# Sheet2.net
KiCad netlist of a schematic drawn in Altium Designer
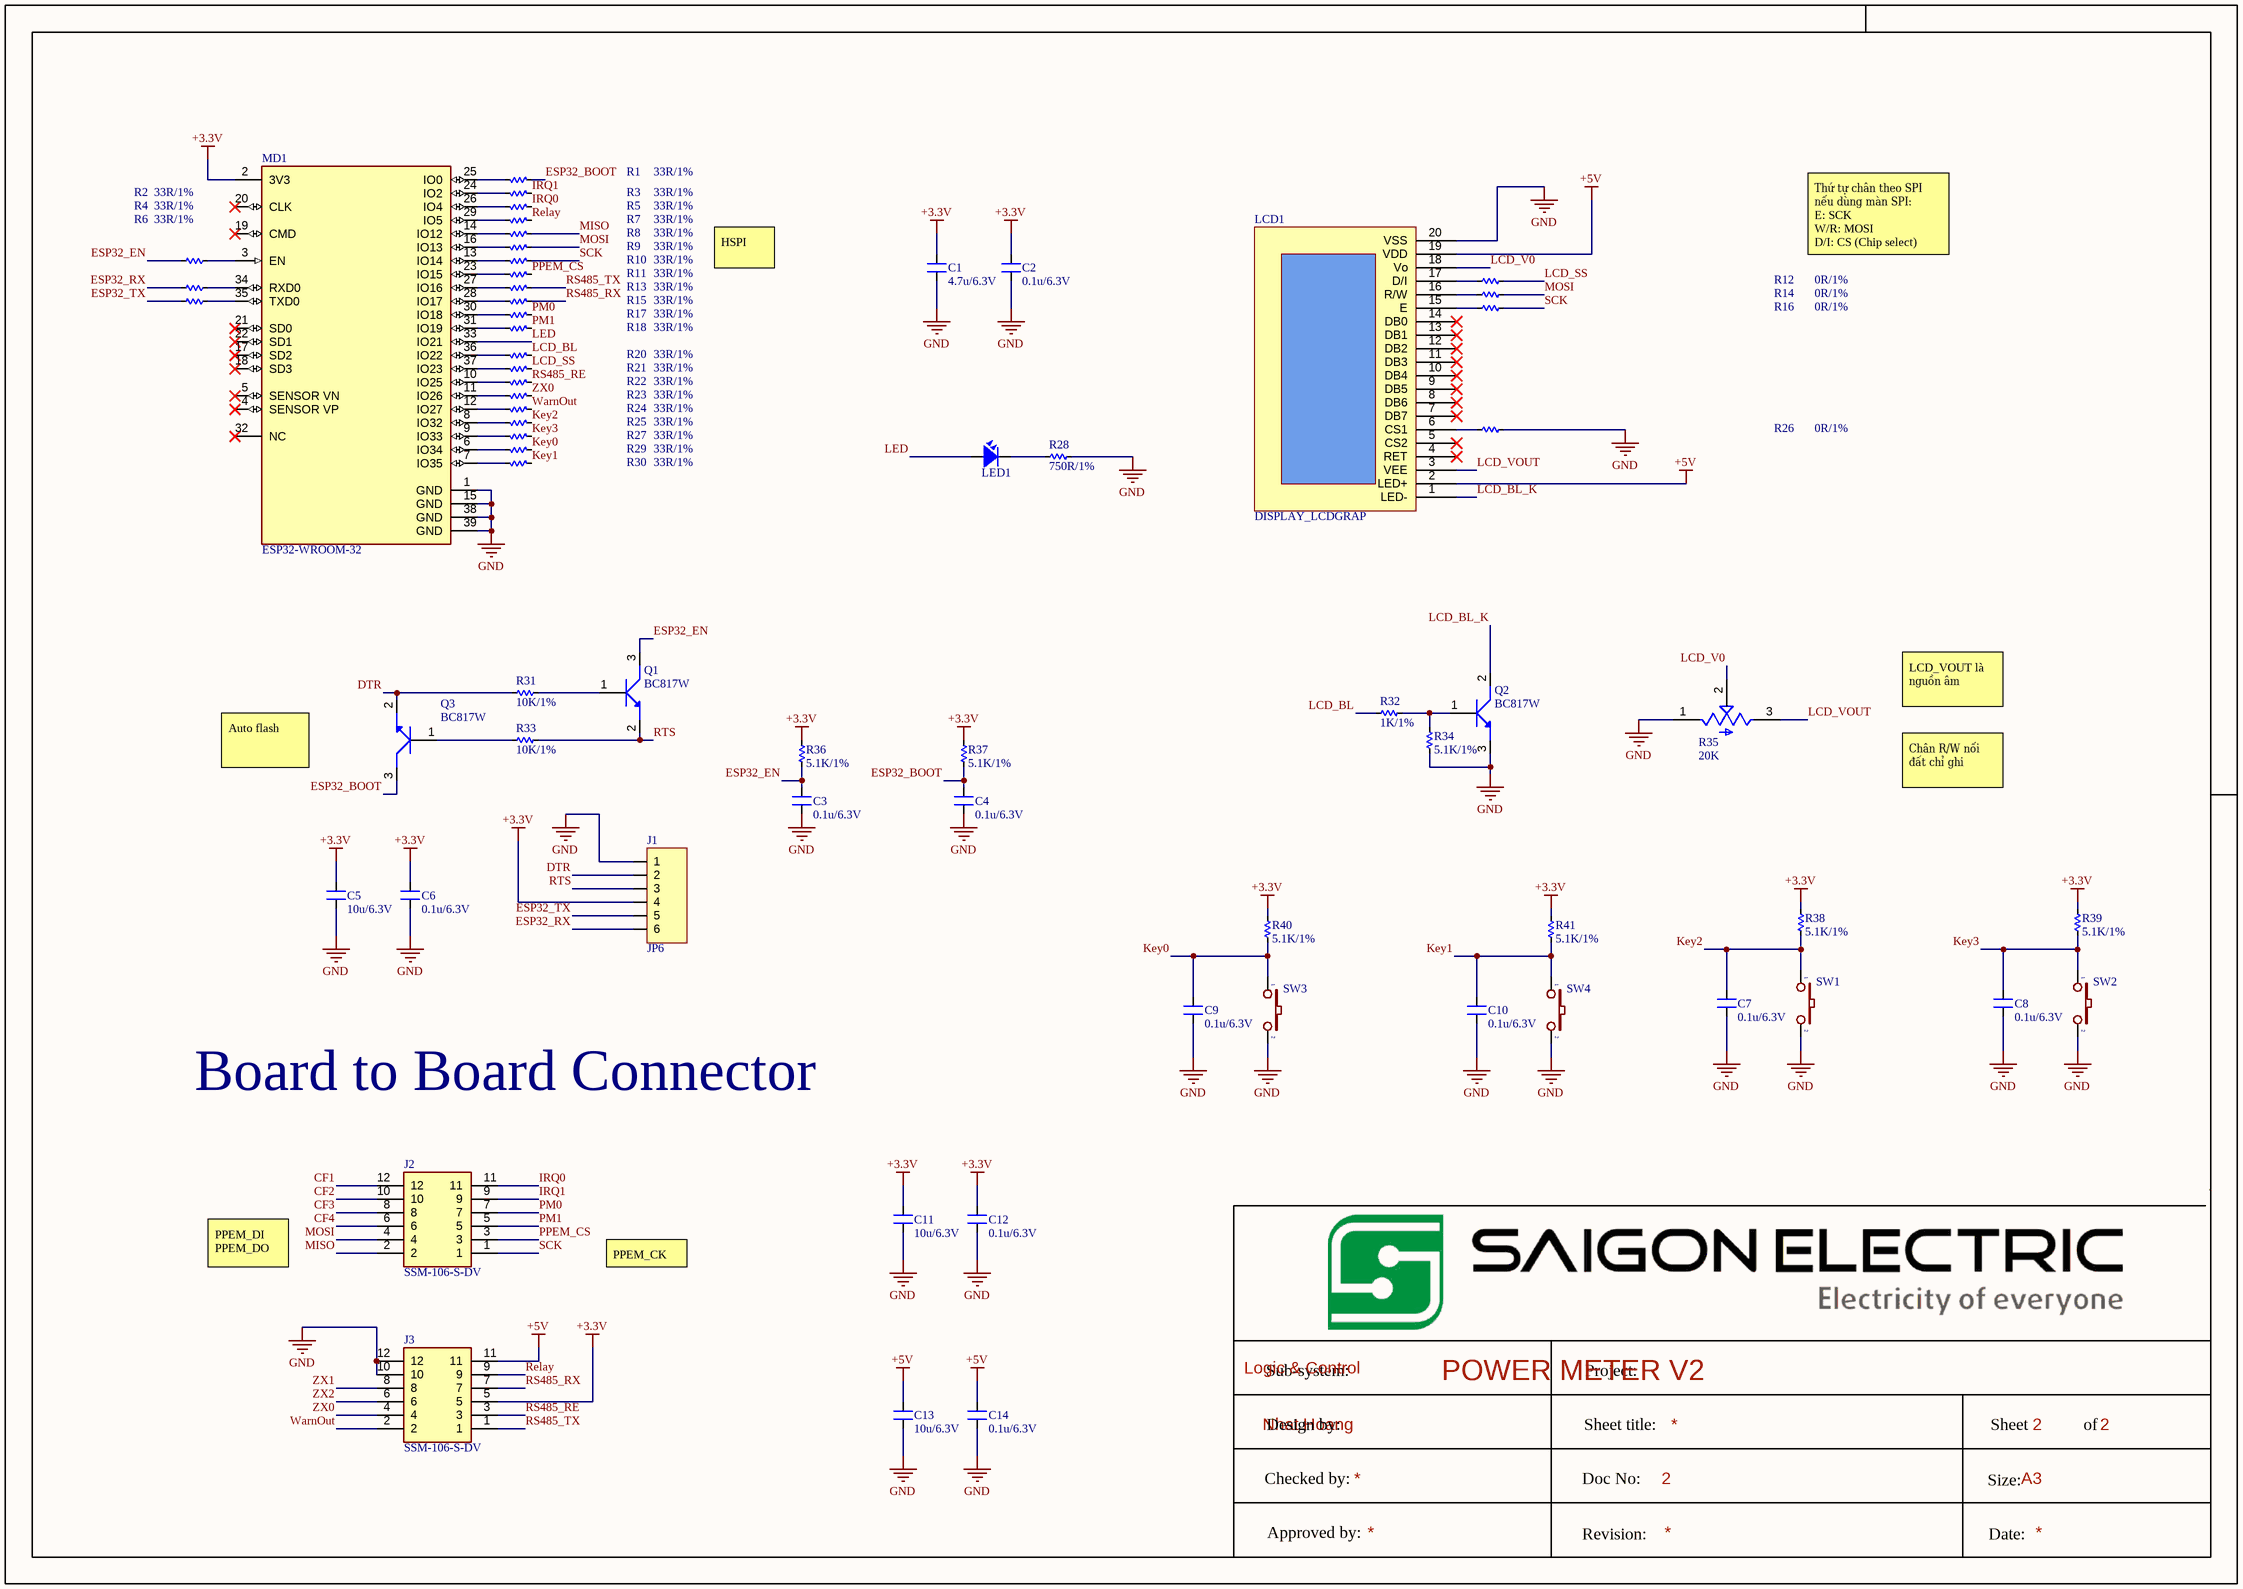
[diagram p0: Sheet2.SchDoc]

(export (version "E")
  (design (tool "Eeschema 10.0.6"))
  (components
    (comp (ref "C1")
      (value "4.7u/6.3V")
      (footprint "CAP_C_2012X110")
      (libsource (lib "DAK_Altium_Integrated_Lib") (part "CAP_SMD"))
    )
    (comp (ref "C2")
      (value "0.1u/6.3V")
      (footprint "CAP_C_2012X110")
      (libsource (lib "DAK_Altium_Integrated_Lib") (part "CAP_SMD"))
    )
    (comp (ref "C3")
      (value "0.1u/6.3V")
      (footprint "CAP_C_2012X110")
      (libsource (lib "DAK_Altium_Integrated_Lib") (part "CAP_SMD"))
    )
    (comp (ref "C4")
      (value "0.1u/6.3V")
      (footprint "CAP_C_2012X110")
      (libsource (lib "DAK_Altium_Integrated_Lib") (part "CAP_SMD"))
    )
    (comp (ref "C5")
      (value "10u/6.3V")
      (footprint "CAP_C_2012X110")
      (libsource (lib "DAK_Altium_Integrated_Lib") (part "CAP_SMD"))
    )
    (comp (ref "C6")
      (value "0.1u/6.3V")
      (footprint "CAP_C_2012X110")
      (libsource (lib "DAK_Altium_Integrated_Lib") (part "CAP_SMD"))
    )
    (comp (ref "C7")
      (value "0.1u/6.3V")
      (footprint "CAP_C_2012X110")
      (libsource (lib "DAK_Altium_Integrated_Lib") (part "CAP_SMD"))
    )
    (comp (ref "C8")
      (value "0.1u/6.3V")
      (footprint "CAP_C_2012X110")
      (libsource (lib "DAK_Altium_Integrated_Lib") (part "CAP_SMD"))
    )
    (comp (ref "C9")
      (value "0.1u/6.3V")
      (footprint "CAP_C_2012X110")
      (libsource (lib "DAK_Altium_Integrated_Lib") (part "CAP_SMD"))
    )
    (comp (ref "C10")
      (value "0.1u/6.3V")
      (footprint "CAP_C_2012X110")
      (libsource (lib "DAK_Altium_Integrated_Lib") (part "CAP_SMD"))
    )
    (comp (ref "C11")
      (value "10u/6.3V")
      (footprint "CAP_C_2012X110")
      (libsource (lib "DAK_Altium_Integrated_Lib") (part "CAP_SMD"))
    )
    (comp (ref "C12")
      (value "0.1u/6.3V")
      (footprint "CAP_C_2012X110")
      (libsource (lib "DAK_Altium_Integrated_Lib") (part "CAP_SMD"))
    )
    (comp (ref "C13")
      (value "10u/6.3V")
      (footprint "CAP_C_2012X110")
      (libsource (lib "DAK_Altium_Integrated_Lib") (part "CAP_SMD"))
    )
    (comp (ref "C14")
      (value "0.1u/6.3V")
      (footprint "CAP_C_2012X110")
      (libsource (lib "DAK_Altium_Integrated_Lib") (part "CAP_SMD"))
    )
    (comp (ref "J1")
      (value "JP6")
      (footprint "JP6-C1C")
      (description "WR-PHD 2.54 mm Angled Socket Header")
      (fields
        (field (name "MANUFACTURER") "Würth Elektronik eiSos GmbH")
        (field (name "PARTNO") "613006143121")
        (field (name "CREATED BY") "Karrer Zheng")
      )
      (libsource (lib "Library") (part "JP6"))
    )
    (comp (ref "J2")
      (value "SSM-106-S-DV")
      (footprint "SSM-106-XXX-DV-BE")
      (description "Connector")
      (fields
        (field (name "MANUFACTURER_PART_NUMBER") "SSM-105-S-DV")
        (field (name "MOUSER PART NUMBER") "200-SSM105SDV")
      )
      (libsource (lib "PowerMeter") (part "SSM-106-S-DV"))
    )
    (comp (ref "J3")
      (value "SSM-106-S-DV")
      (footprint "SSM-106-XXX-DV-BE")
      (description "Connector")
      (fields
        (field (name "MANUFACTURER_PART_NUMBER") "SSM-105-S-DV")
        (field (name "MOUSER PART NUMBER") "200-SSM105SDV")
      )
      (libsource (lib "PowerMeter") (part "SSM-106-S-DV"))
    )
    (comp (ref "LCD1")
      (value "DISPLAY_LCDGRAP")
      (footprint "LCD_GRAP_20PIN")
      (description "Display 128x64pixel")
      (fields
        (field (name "MANUFACTURER") "Newhaven Display")
        (field (name "MANUFACTURER PART NUMBER") "NHD-12864AZ-NSW-BBW-TR")
      )
      (libsource (lib "PowerMeter") (part "DISPLAY_LCDGRAP"))
    )
    (comp (ref "LED1") (value "LED") (footprint "LED-0805-Blue") (libsource (lib "Library") (part "LED SMD")))
    (comp (ref "MD1")
      (value "ESP32-WROOM-32")
      (footprint "FP-ESP32-WROOM-32-MFG")
      (description "RX TXRX MOD WIFI SURFACE MOUNT")
      (libsource (lib "PowerMeter") (part "CMP-194065-000008-1"))
    )
    (comp (ref "Q1")
      (value "BC817W")
      (footprint "SOT95P237X112-3N")
      (libsource (lib "PowerMeter") (part "BJT_NPN"))
    )
    (comp (ref "Q2") (value "BC817W") (footprint "SOT95P237X112-3N") (libsource (lib "") (part "BJT_NPN_1")))
    (comp (ref "Q3")
      (value "BC817W")
      (footprint "SOT95P237X112-3N")
      (libsource (lib "PowerMeter") (part "BJT_NPN"))
    )
    (comp (ref "R1")
      (value "33R/1%")
      (footprint "RES_C_2012X65")
      (description "Resistor")
      (fields
        (field (name "MANUFACTURER") "Generic Components")
        (field (name "PUBLISHER") "Altium Hobart Technology Centre")
      )
      (libsource (lib "Library") (part "Res-SMD"))
    )
    (comp (ref "R2")
      (value "33R/1%")
      (footprint "RES_C_2012X65")
      (description "Resistor")
      (fields
        (field (name "MANUFACTURER") "Generic Components")
        (field (name "PUBLISHER") "Altium Hobart Technology Centre")
      )
      (libsource (lib "Library") (part "Res-SMD"))
    )
    (comp (ref "R3")
      (value "33R/1%")
      (footprint "RES_C_2012X65")
      (description "Resistor")
      (fields
        (field (name "MANUFACTURER") "Generic Components")
        (field (name "PUBLISHER") "Altium Hobart Technology Centre")
      )
      (libsource (lib "Library") (part "Res-SMD"))
    )
    (comp (ref "R4")
      (value "33R/1%")
      (footprint "RES_C_2012X65")
      (description "Resistor")
      (fields
        (field (name "MANUFACTURER") "Generic Components")
        (field (name "PUBLISHER") "Altium Hobart Technology Centre")
      )
      (libsource (lib "Library") (part "Res-SMD"))
    )
    (comp (ref "R5")
      (value "33R/1%")
      (footprint "RES_C_2012X65")
      (description "Resistor")
      (fields
        (field (name "MANUFACTURER") "Generic Components")
        (field (name "PUBLISHER") "Altium Hobart Technology Centre")
      )
      (libsource (lib "Library") (part "Res-SMD"))
    )
    (comp (ref "R6")
      (value "33R/1%")
      (footprint "RES_C_2012X65")
      (description "Resistor")
      (fields
        (field (name "MANUFACTURER") "Generic Components")
        (field (name "PUBLISHER") "Altium Hobart Technology Centre")
      )
      (libsource (lib "Library") (part "Res-SMD"))
    )
    (comp (ref "R7")
      (value "33R/1%")
      (footprint "RES_C_2012X65")
      (description "Resistor")
      (fields
        (field (name "MANUFACTURER") "Generic Components")
        (field (name "PUBLISHER") "Altium Hobart Technology Centre")
      )
      (libsource (lib "Library") (part "Res-SMD"))
    )
    (comp (ref "R8")
      (value "33R/1%")
      (footprint "RES_C_2012X65")
      (description "Resistor")
      (fields
        (field (name "MANUFACTURER") "Generic Components")
        (field (name "PUBLISHER") "Altium Hobart Technology Centre")
      )
      (libsource (lib "Library") (part "Res-SMD"))
    )
    (comp (ref "R9")
      (value "33R/1%")
      (footprint "RES_C_2012X65")
      (description "Resistor")
      (fields
        (field (name "MANUFACTURER") "Generic Components")
        (field (name "PUBLISHER") "Altium Hobart Technology Centre")
      )
      (libsource (lib "Library") (part "Res-SMD"))
    )
    (comp (ref "R10")
      (value "33R/1%")
      (footprint "RES_C_2012X65")
      (description "Resistor")
      (fields
        (field (name "MANUFACTURER") "Generic Components")
        (field (name "PUBLISHER") "Altium Hobart Technology Centre")
      )
      (libsource (lib "Library") (part "Res-SMD"))
    )
    (comp (ref "R11")
      (value "33R/1%")
      (footprint "RES_C_2012X65")
      (description "Resistor")
      (fields
        (field (name "MANUFACTURER") "Generic Components")
        (field (name "PUBLISHER") "Altium Hobart Technology Centre")
      )
      (libsource (lib "Library") (part "Res-SMD"))
    )
    (comp (ref "R12")
      (value "0R/1%")
      (footprint "RES_C_2012X65")
      (description "Resistor")
      (fields
        (field (name "MANUFACTURER") "Generic Components")
        (field (name "PUBLISHER") "Altium Hobart Technology Centre")
      )
      (libsource (lib "Library") (part "Res-SMD"))
    )
    (comp (ref "R13")
      (value "33R/1%")
      (footprint "RES_C_2012X65")
      (description "Resistor")
      (fields
        (field (name "MANUFACTURER") "Generic Components")
        (field (name "PUBLISHER") "Altium Hobart Technology Centre")
      )
      (libsource (lib "Library") (part "Res-SMD"))
    )
    (comp (ref "R14")
      (value "0R/1%")
      (footprint "RES_C_2012X65")
      (description "Resistor")
      (fields
        (field (name "MANUFACTURER") "Generic Components")
        (field (name "PUBLISHER") "Altium Hobart Technology Centre")
      )
      (libsource (lib "Library") (part "Res-SMD"))
    )
    (comp (ref "R15")
      (value "33R/1%")
      (footprint "RES_C_2012X65")
      (description "Resistor")
      (fields
        (field (name "MANUFACTURER") "Generic Components")
        (field (name "PUBLISHER") "Altium Hobart Technology Centre")
      )
      (libsource (lib "Library") (part "Res-SMD"))
    )
    (comp (ref "R16")
      (value "0R/1%")
      (footprint "RES_C_2012X65")
      (description "Resistor")
      (fields
        (field (name "MANUFACTURER") "Generic Components")
        (field (name "PUBLISHER") "Altium Hobart Technology Centre")
      )
      (libsource (lib "Library") (part "Res-SMD"))
    )
    (comp (ref "R17")
      (value "33R/1%")
      (footprint "RES_C_2012X65")
      (description "Resistor")
      (fields
        (field (name "MANUFACTURER") "Generic Components")
        (field (name "PUBLISHER") "Altium Hobart Technology Centre")
      )
      (libsource (lib "Library") (part "Res-SMD"))
    )
    (comp (ref "R18")
      (value "33R/1%")
      (footprint "RES_C_2012X65")
      (description "Resistor")
      (fields
        (field (name "MANUFACTURER") "Generic Components")
        (field (name "PUBLISHER") "Altium Hobart Technology Centre")
      )
      (libsource (lib "Library") (part "Res-SMD"))
    )
    (comp (ref "R20")
      (value "33R/1%")
      (footprint "RES_C_2012X65")
      (description "Resistor")
      (fields
        (field (name "MANUFACTURER") "Generic Components")
        (field (name "PUBLISHER") "Altium Hobart Technology Centre")
      )
      (libsource (lib "Library") (part "Res-SMD"))
    )
    (comp (ref "R21")
      (value "33R/1%")
      (footprint "RES_C_2012X65")
      (description "Resistor")
      (fields
        (field (name "MANUFACTURER") "Generic Components")
        (field (name "PUBLISHER") "Altium Hobart Technology Centre")
      )
      (libsource (lib "Library") (part "Res-SMD"))
    )
    (comp (ref "R22")
      (value "33R/1%")
      (footprint "RES_C_2012X65")
      (description "Resistor")
      (fields
        (field (name "MANUFACTURER") "Generic Components")
        (field (name "PUBLISHER") "Altium Hobart Technology Centre")
      )
      (libsource (lib "Library") (part "Res-SMD"))
    )
    (comp (ref "R23")
      (value "33R/1%")
      (footprint "RES_C_2012X65")
      (description "Resistor")
      (fields
        (field (name "MANUFACTURER") "Generic Components")
        (field (name "PUBLISHER") "Altium Hobart Technology Centre")
      )
      (libsource (lib "Library") (part "Res-SMD"))
    )
    (comp (ref "R24")
      (value "33R/1%")
      (footprint "RES_C_2012X65")
      (description "Resistor")
      (fields
        (field (name "MANUFACTURER") "Generic Components")
        (field (name "PUBLISHER") "Altium Hobart Technology Centre")
      )
      (libsource (lib "Library") (part "Res-SMD"))
    )
    (comp (ref "R25")
      (value "33R/1%")
      (footprint "RES_C_2012X65")
      (description "Resistor")
      (fields
        (field (name "MANUFACTURER") "Generic Components")
        (field (name "PUBLISHER") "Altium Hobart Technology Centre")
      )
      (libsource (lib "Library") (part "Res-SMD"))
    )
    (comp (ref "R26")
      (value "0R/1%")
      (footprint "RES_C_2012X65")
      (description "Resistor")
      (fields
        (field (name "MANUFACTURER") "Generic Components")
        (field (name "PUBLISHER") "Altium Hobart Technology Centre")
      )
      (libsource (lib "Library") (part "Res-SMD"))
    )
    (comp (ref "R27")
      (value "33R/1%")
      (footprint "RES_C_2012X65")
      (description "Resistor")
      (fields
        (field (name "MANUFACTURER") "Generic Components")
        (field (name "PUBLISHER") "Altium Hobart Technology Centre")
      )
      (libsource (lib "Library") (part "Res-SMD"))
    )
    (comp (ref "R28")
      (value "750R/1%")
      (footprint "RES_C_2012X65")
      (description "Resistor")
      (fields
        (field (name "MANUFACTURER") "Generic Components")
        (field (name "PUBLISHER") "Altium Hobart Technology Centre")
      )
      (libsource (lib "Library") (part "Res-SMD"))
    )
    (comp (ref "R29")
      (value "33R/1%")
      (footprint "RES_C_2012X65")
      (description "Resistor")
      (fields
        (field (name "MANUFACTURER") "Generic Components")
        (field (name "PUBLISHER") "Altium Hobart Technology Centre")
      )
      (libsource (lib "Library") (part "Res-SMD"))
    )
    (comp (ref "R30")
      (value "33R/1%")
      (footprint "RES_C_2012X65")
      (description "Resistor")
      (fields
        (field (name "MANUFACTURER") "Generic Components")
        (field (name "PUBLISHER") "Altium Hobart Technology Centre")
      )
      (libsource (lib "Library") (part "Res-SMD"))
    )
    (comp (ref "R31")
      (value "10K/1%")
      (footprint "RES_C_2012X65")
      (description "Resistor")
      (fields
        (field (name "MANUFACTURER") "Generic Components")
        (field (name "PUBLISHER") "Altium Hobart Technology Centre")
      )
      (libsource (lib "Library") (part "Res-SMD"))
    )
    (comp (ref "R32")
      (value "1K/1%")
      (footprint "RES_C_2012X65")
      (description "Resistor")
      (fields
        (field (name "MANUFACTURER") "Generic Components")
        (field (name "PUBLISHER") "Altium Hobart Technology Centre")
      )
      (libsource (lib "Library") (part "Res-SMD"))
    )
    (comp (ref "R33")
      (value "10K/1%")
      (footprint "RES_C_2012X65")
      (description "Resistor")
      (fields
        (field (name "MANUFACTURER") "Generic Components")
        (field (name "PUBLISHER") "Altium Hobart Technology Centre")
      )
      (libsource (lib "Library") (part "Res-SMD"))
    )
    (comp (ref "R34")
      (value "5.1K/1%")
      (footprint "RES_C_2012X65")
      (description "Resistor")
      (fields
        (field (name "MANUFACTURER") "Generic Components")
        (field (name "PUBLISHER") "Altium Hobart Technology Centre")
      )
      (libsource (lib "Library") (part "Res-SMD"))
    )
    (comp (ref "R35")
      (value "20K")
      (footprint "TRIM_TC33X-2-103E")
      (description "10 kOhms 0.1W, 1/10W J Lead Surface Mount Trimmer Potentiometer Cermet 1 Turn Top Adjustment")
      (fields (field (name "MP") "TC33X-2-103E") (field (name "MF") "Bourns"))
      (libsource (lib "TC33X-2-103E") (part "TC33X-2-103E"))
    )
    (comp (ref "R36")
      (value "5.1K/1%")
      (footprint "RES_C_2012X65")
      (description "Resistor")
      (fields
        (field (name "MANUFACTURER") "Generic Components")
        (field (name "PUBLISHER") "Altium Hobart Technology Centre")
      )
      (libsource (lib "Library") (part "Res-SMD"))
    )
    (comp (ref "R37")
      (value "5.1K/1%")
      (footprint "RES_C_2012X65")
      (description "Resistor")
      (fields
        (field (name "MANUFACTURER") "Generic Components")
        (field (name "PUBLISHER") "Altium Hobart Technology Centre")
      )
      (libsource (lib "Library") (part "Res-SMD"))
    )
    (comp (ref "R38")
      (value "5.1K/1%")
      (footprint "RES_C_2012X65")
      (description "Resistor")
      (fields
        (field (name "MANUFACTURER") "Generic Components")
        (field (name "PUBLISHER") "Altium Hobart Technology Centre")
      )
      (libsource (lib "Library") (part "Res-SMD"))
    )
    (comp (ref "R39")
      (value "5.1K/1%")
      (footprint "RES_C_2012X65")
      (description "Resistor")
      (fields
        (field (name "MANUFACTURER") "Generic Components")
        (field (name "PUBLISHER") "Altium Hobart Technology Centre")
      )
      (libsource (lib "Library") (part "Res-SMD"))
    )
    (comp (ref "R40")
      (value "5.1K/1%")
      (footprint "RES_C_2012X65")
      (description "Resistor")
      (fields
        (field (name "MANUFACTURER") "Generic Components")
        (field (name "PUBLISHER") "Altium Hobart Technology Centre")
      )
      (libsource (lib "Library") (part "Res-SMD"))
    )
    (comp (ref "R41")
      (value "5.1K/1%")
      (footprint "RES_C_2012X65")
      (description "Resistor")
      (fields
        (field (name "MANUFACTURER") "Generic Components")
        (field (name "PUBLISHER") "Altium Hobart Technology Centre")
      )
      (libsource (lib "Library") (part "Res-SMD"))
    )
    (comp (ref "SW1")
      (value "~")
      (footprint "SW2-SMD")
      (description "Switch button 2 pin")
      (libsource (lib "Library") (part "SW2"))
    )
    (comp (ref "SW2")
      (value "~")
      (footprint "SW2-SMD")
      (description "Switch button 2 pin")
      (libsource (lib "Library") (part "SW2"))
    )
    (comp (ref "SW3")
      (value "~")
      (footprint "SW2-SMD")
      (description "Switch button 2 pin")
      (libsource (lib "Library") (part "SW2"))
    )
    (comp (ref "SW4")
      (value "~")
      (footprint "SW2-SMD")
      (description "Switch button 2 pin")
      (libsource (lib "Library") (part "SW2"))
    )
  )
  (nets
    (net (code "1") (name "+3.3V") (class "Default")
      (node (ref "C1") (pin "2") (pinfunction "2_2") (pintype "passive"))
      (node (ref "C11") (pin "2") (pinfunction "2_2") (pintype "passive"))
      (node (ref "C12") (pin "2") (pinfunction "2_2") (pintype "passive"))
      (node (ref "C2") (pin "2") (pinfunction "2_2") (pintype "passive"))
      (node (ref "C5") (pin "2") (pinfunction "2_2") (pintype "passive"))
      (node (ref "C6") (pin "2") (pinfunction "2_2") (pintype "passive"))
      (node (ref "J1") (pin "4") (pinfunction "4_4") (pintype "passive"))
      (node (ref "J3") (pin "5") (pinfunction "5_5") (pintype "passive"))
      (node (ref "MD1") (pin "2") (pinfunction "3V3_2") (pintype "power_in"))
      (node (ref "R36") (pin "2") (pinfunction "2_2") (pintype "passive"))
      (node (ref "R37") (pin "2") (pinfunction "2_2") (pintype "passive"))
      (node (ref "R38") (pin "2") (pinfunction "2_2") (pintype "passive"))
      (node (ref "R39") (pin "2") (pinfunction "2_2") (pintype "passive"))
      (node (ref "R40") (pin "2") (pinfunction "2_2") (pintype "passive"))
      (node (ref "R41") (pin "2") (pinfunction "2_2") (pintype "passive"))
    )
    (net (code "2") (name "+5V") (class "Default")
      (node (ref "C13") (pin "2") (pinfunction "2_2") (pintype "passive"))
      (node (ref "C14") (pin "2") (pinfunction "2_2") (pintype "passive"))
      (node (ref "J3") (pin "11") (pinfunction "11_11") (pintype "passive"))
      (node (ref "LCD1") (pin "19") (pinfunction "VDD_19") (pintype "power_in"))
      (node (ref "LCD1") (pin "2") (pinfunction "LED+_2") (pintype "power_in"))
    )
    (net (code "3") (name "/CF1") (class "Default")
      (node (ref "J2") (pin "12") (pinfunction "12_12") (pintype "passive"))
    )
    (net (code "4") (name "/CF2") (class "Default")
      (node (ref "J2") (pin "10") (pinfunction "10_10") (pintype "passive"))
    )
    (net (code "5") (name "/CF3") (class "Default")
      (node (ref "J2") (pin "8") (pinfunction "8_8") (pintype "passive"))
    )
    (net (code "6") (name "/CF4") (class "Default")
      (node (ref "J2") (pin "6") (pinfunction "6_6") (pintype "passive"))
    )
    (net (code "7") (name "/DTR") (class "Default")
      (node (ref "J1") (pin "2") (pinfunction "2_2") (pintype "passive"))
      (node (ref "Q3") (pin "2") (pinfunction "E_2") (pintype "passive"))
      (node (ref "R31") (pin "2") (pinfunction "2_2") (pintype "passive"))
    )
    (net (code "8") (name "/ESP32_BOOT") (class "Default")
      (node (ref "C4") (pin "2") (pinfunction "2_2") (pintype "passive"))
      (node (ref "Q3") (pin "3") (pinfunction "C_3") (pintype "passive"))
      (node (ref "R1") (pin "2") (pinfunction "2_2") (pintype "passive"))
      (node (ref "R37") (pin "1") (pinfunction "1_1") (pintype "passive"))
    )
    (net (code "9") (name "/ESP32_EN") (class "Default")
      (node (ref "C3") (pin "2") (pinfunction "2_2") (pintype "passive"))
      (node (ref "Q1") (pin "3") (pinfunction "C_3") (pintype "passive"))
      (node (ref "R2") (pin "2") (pinfunction "2_2") (pintype "passive"))
      (node (ref "R36") (pin "1") (pinfunction "1_1") (pintype "passive"))
    )
    (net (code "10") (name "/ESP32_RX") (class "Default")
      (node (ref "J1") (pin "6") (pinfunction "6_6") (pintype "passive"))
      (node (ref "R4") (pin "2") (pinfunction "2_2") (pintype "passive"))
    )
    (net (code "11") (name "/ESP32_TX") (class "Default")
      (node (ref "J1") (pin "5") (pinfunction "5_5") (pintype "passive"))
      (node (ref "R6") (pin "2") (pinfunction "2_2") (pintype "passive"))
    )
    (net (code "12") (name "/IRQ0") (class "Default")
      (node (ref "J2") (pin "11") (pinfunction "11_11") (pintype "passive"))
      (node (ref "R5") (pin "2") (pinfunction "2_2") (pintype "passive"))
    )
    (net (code "13") (name "/IRQ1") (class "Default")
      (node (ref "J2") (pin "9") (pinfunction "9_9") (pintype "passive"))
      (node (ref "R3") (pin "2") (pinfunction "2_2") (pintype "passive"))
    )
    (net (code "14") (name "/Key0") (class "Default")
      (node (ref "C9") (pin "2") (pinfunction "2_2") (pintype "passive"))
      (node (ref "R29") (pin "2") (pinfunction "2_2") (pintype "passive"))
      (node (ref "R40") (pin "1") (pinfunction "1_1") (pintype "passive"))
      (node (ref "SW3") (pin "1") (pinfunction "1_1") (pintype "passive"))
    )
    (net (code "15") (name "/Key1") (class "Default")
      (node (ref "C10") (pin "2") (pinfunction "2_2") (pintype "passive"))
      (node (ref "R30") (pin "2") (pinfunction "2_2") (pintype "passive"))
      (node (ref "R41") (pin "1") (pinfunction "1_1") (pintype "passive"))
      (node (ref "SW4") (pin "1") (pinfunction "1_1") (pintype "passive"))
    )
    (net (code "16") (name "/Key2") (class "Default")
      (node (ref "C7") (pin "2") (pinfunction "2_2") (pintype "passive"))
      (node (ref "R25") (pin "2") (pinfunction "2_2") (pintype "passive"))
      (node (ref "R38") (pin "1") (pinfunction "1_1") (pintype "passive"))
      (node (ref "SW1") (pin "1") (pinfunction "1_1") (pintype "passive"))
    )
    (net (code "17") (name "/Key3") (class "Default")
      (node (ref "C8") (pin "2") (pinfunction "2_2") (pintype "passive"))
      (node (ref "R27") (pin "2") (pinfunction "2_2") (pintype "passive"))
      (node (ref "R39") (pin "1") (pinfunction "1_1") (pintype "passive"))
      (node (ref "SW2") (pin "1") (pinfunction "1_1") (pintype "passive"))
    )
    (net (code "18") (name "/LCD_BL") (class "Default")
      (node (ref "R20") (pin "2") (pinfunction "2_2") (pintype "passive"))
      (node (ref "R32") (pin "1") (pinfunction "1_1") (pintype "passive"))
    )
    (net (code "19") (name "/LCD_BL_K") (class "Default")
      (node (ref "LCD1") (pin "1") (pinfunction "LED-_1") (pintype "power_in"))
      (node (ref "Q2") (pin "2") (pinfunction "E_2") (pintype "passive"))
    )
    (net (code "20") (name "/LCD_SS") (class "Default")
      (node (ref "R12") (pin "2") (pinfunction "2_2") (pintype "passive"))
      (node (ref "R21") (pin "2") (pinfunction "2_2") (pintype "passive"))
    )
    (net (code "21") (name "/LCD_V0") (class "Default")
      (node (ref "LCD1") (pin "18") (pinfunction "Vo_18") (pintype "power_in"))
      (node (ref "R35") (pin "2") (pinfunction "W_2") (pintype "passive"))
    )
    (net (code "22") (name "/LCD_VOUT") (class "Default")
      (node (ref "LCD1") (pin "3") (pinfunction "VEE_3") (pintype "power_in"))
      (node (ref "R35") (pin "3") (pinfunction "CW_3") (pintype "passive"))
    )
    (net (code "23") (name "/LED") (class "Default")
      (node (ref "LED1") (pin "1") (pinfunction "1_1") (pintype "passive"))
      (node (ref "MD1") (pin "33") (pinfunction "IO21_33") (pintype "bidirectional"))
    )
    (net (code "24") (name "/MISO") (class "Default")
      (node (ref "J2") (pin "2") (pinfunction "2_2") (pintype "passive"))
      (node (ref "R8") (pin "2") (pinfunction "2_2") (pintype "passive"))
    )
    (net (code "25") (name "/MOSI") (class "Default")
      (node (ref "J2") (pin "4") (pinfunction "4_4") (pintype "passive"))
      (node (ref "R14") (pin "2") (pinfunction "2_2") (pintype "passive"))
      (node (ref "R9") (pin "2") (pinfunction "2_2") (pintype "passive"))
    )
    (net (code "26") (name "/PM0") (class "Default")
      (node (ref "J2") (pin "7") (pinfunction "7_7") (pintype "passive"))
      (node (ref "R17") (pin "2") (pinfunction "2_2") (pintype "passive"))
    )
    (net (code "27") (name "/PM1") (class "Default")
      (node (ref "J2") (pin "5") (pinfunction "5_5") (pintype "passive"))
      (node (ref "R18") (pin "2") (pinfunction "2_2") (pintype "passive"))
    )
    (net (code "28") (name "/PPEM_CS") (class "Default")
      (node (ref "J2") (pin "3") (pinfunction "3_3") (pintype "passive"))
      (node (ref "R11") (pin "2") (pinfunction "2_2") (pintype "passive"))
    )
    (net (code "29") (name "/RS485_RE") (class "Default")
      (node (ref "J3") (pin "3") (pinfunction "3_3") (pintype "passive"))
      (node (ref "R22") (pin "2") (pinfunction "2_2") (pintype "passive"))
    )
    (net (code "30") (name "/RS485_RX") (class "Default")
      (node (ref "J3") (pin "7") (pinfunction "7_7") (pintype "passive"))
      (node (ref "R15") (pin "2") (pinfunction "2_2") (pintype "passive"))
    )
    (net (code "31") (name "/RS485_TX") (class "Default")
      (node (ref "J3") (pin "1") (pinfunction "1_1") (pintype "passive"))
      (node (ref "R13") (pin "2") (pinfunction "2_2") (pintype "passive"))
    )
    (net (code "32") (name "/RTS") (class "Default")
      (node (ref "J1") (pin "3") (pinfunction "3_3") (pintype "passive"))
      (node (ref "Q1") (pin "2") (pinfunction "E_2") (pintype "passive"))
      (node (ref "R33") (pin "1") (pinfunction "1_1") (pintype "passive"))
    )
    (net (code "33") (name "/Relay") (class "Default")
      (node (ref "J3") (pin "9") (pinfunction "9_9") (pintype "passive"))
      (node (ref "R7") (pin "2") (pinfunction "2_2") (pintype "passive"))
    )
    (net (code "34") (name "/SCK") (class "Default")
      (node (ref "J2") (pin "1") (pinfunction "1_1") (pintype "passive"))
      (node (ref "R10") (pin "2") (pinfunction "2_2") (pintype "passive"))
      (node (ref "R16") (pin "2") (pinfunction "2_2") (pintype "passive"))
    )
    (net (code "35") (name "/WarnOut") (class "Default")
      (node (ref "J3") (pin "2") (pinfunction "2_2") (pintype "passive"))
      (node (ref "R24") (pin "2") (pinfunction "2_2") (pintype "passive"))
    )
    (net (code "36") (name "/ZX0") (class "Default")
      (node (ref "J3") (pin "4") (pinfunction "4_4") (pintype "passive"))
      (node (ref "R23") (pin "2") (pinfunction "2_2") (pintype "passive"))
    )
    (net (code "37") (name "/ZX1") (class "Default")
      (node (ref "J3") (pin "8") (pinfunction "8_8") (pintype "passive"))
    )
    (net (code "38") (name "/ZX2") (class "Default")
      (node (ref "J3") (pin "6") (pinfunction "6_6") (pintype "passive"))
    )
    (net (code "39") (name "GND") (class "Default")
      (node (ref "C1") (pin "1") (pinfunction "1_1") (pintype "passive"))
      (node (ref "C10") (pin "1") (pinfunction "1_1") (pintype "passive"))
      (node (ref "C11") (pin "1") (pinfunction "1_1") (pintype "passive"))
      (node (ref "C12") (pin "1") (pinfunction "1_1") (pintype "passive"))
      (node (ref "C13") (pin "1") (pinfunction "1_1") (pintype "passive"))
      (node (ref "C14") (pin "1") (pinfunction "1_1") (pintype "passive"))
      (node (ref "C2") (pin "1") (pinfunction "1_1") (pintype "passive"))
      (node (ref "C3") (pin "1") (pinfunction "1_1") (pintype "passive"))
      (node (ref "C4") (pin "1") (pinfunction "1_1") (pintype "passive"))
      (node (ref "C5") (pin "1") (pinfunction "1_1") (pintype "passive"))
      (node (ref "C6") (pin "1") (pinfunction "1_1") (pintype "passive"))
      (node (ref "C7") (pin "1") (pinfunction "1_1") (pintype "passive"))
      (node (ref "C8") (pin "1") (pinfunction "1_1") (pintype "passive"))
      (node (ref "C9") (pin "1") (pinfunction "1_1") (pintype "passive"))
      (node (ref "J1") (pin "1") (pinfunction "1_1") (pintype "passive"))
      (node (ref "J3") (pin "10") (pinfunction "10_10") (pintype "passive"))
      (node (ref "J3") (pin "12") (pinfunction "12_12") (pintype "passive"))
      (node (ref "LCD1") (pin "20") (pinfunction "VSS_20") (pintype "power_in"))
      (node (ref "MD1") (pin "1") (pinfunction "GND_1") (pintype "power_in"))
      (node (ref "MD1") (pin "15") (pinfunction "GND_15") (pintype "power_in"))
      (node (ref "MD1") (pin "38") (pinfunction "GND_38") (pintype "power_in"))
      (node (ref "MD1") (pin "39") (pinfunction "GND_39") (pintype "power_in"))
      (node (ref "Q2") (pin "3") (pinfunction "C_3") (pintype "passive"))
      (node (ref "R26") (pin "2") (pinfunction "2_2") (pintype "passive"))
      (node (ref "R28") (pin "2") (pinfunction "2_2") (pintype "passive"))
      (node (ref "R34") (pin "1") (pinfunction "1_1") (pintype "passive"))
      (node (ref "R35") (pin "1") (pinfunction "CCW_1") (pintype "passive"))
      (node (ref "SW1") (pin "2") (pinfunction "2_2") (pintype "passive"))
      (node (ref "SW2") (pin "2") (pinfunction "2_2") (pintype "passive"))
      (node (ref "SW3") (pin "2") (pinfunction "2_2") (pintype "passive"))
      (node (ref "SW4") (pin "2") (pinfunction "2_2") (pintype "passive"))
    )
    (net (code "40") (name "Net-(LCD1-CS1)") (class "Default")
      (node (ref "LCD1") (pin "6") (pinfunction "CS1_6") (pintype "passive"))
      (node (ref "R26") (pin "1") (pinfunction "1_1") (pintype "passive"))
    )
    (net (code "41") (name "Net-(LCD1-D{slash}I)") (class "Default")
      (node (ref "LCD1") (pin "17") (pinfunction "D/I_17") (pintype "passive"))
      (node (ref "R12") (pin "1") (pinfunction "1_1") (pintype "passive"))
    )
    (net (code "42") (name "Net-(LCD1-E)") (class "Default")
      (node (ref "LCD1") (pin "15") (pinfunction "E_15") (pintype "passive"))
      (node (ref "R16") (pin "1") (pinfunction "1_1") (pintype "passive"))
    )
    (net (code "43") (name "Net-(LCD1-R{slash}W)") (class "Default")
      (node (ref "LCD1") (pin "16") (pinfunction "R/W_16") (pintype "passive"))
      (node (ref "R14") (pin "1") (pinfunction "1_1") (pintype "passive"))
    )
    (net (code "44") (name "Net-(LED1-Pad2)") (class "Default")
      (node (ref "LED1") (pin "2") (pinfunction "2_2") (pintype "passive"))
      (node (ref "R28") (pin "1") (pinfunction "1_1") (pintype "passive"))
    )
    (net (code "45") (name "Net-(MD1-EN)") (class "Default")
      (node (ref "MD1") (pin "3") (pinfunction "EN_3") (pintype "input"))
      (node (ref "R2") (pin "1") (pinfunction "1_1") (pintype "passive"))
    )
    (net (code "46") (name "Net-(MD1-IO0)") (class "Default")
      (node (ref "MD1") (pin "25") (pinfunction "IO0_25") (pintype "bidirectional"))
      (node (ref "R1") (pin "1") (pinfunction "1_1") (pintype "passive"))
    )
    (net (code "47") (name "Net-(MD1-IO2)") (class "Default")
      (node (ref "MD1") (pin "24") (pinfunction "IO2_24") (pintype "bidirectional"))
      (node (ref "R3") (pin "1") (pinfunction "1_1") (pintype "passive"))
    )
    (net (code "48") (name "Net-(MD1-IO4)") (class "Default")
      (node (ref "MD1") (pin "26") (pinfunction "IO4_26") (pintype "bidirectional"))
      (node (ref "R5") (pin "1") (pinfunction "1_1") (pintype "passive"))
    )
    (net (code "49") (name "Net-(MD1-IO5)") (class "Default")
      (node (ref "MD1") (pin "29") (pinfunction "IO5_29") (pintype "bidirectional"))
      (node (ref "R7") (pin "1") (pinfunction "1_1") (pintype "passive"))
    )
    (net (code "50") (name "Net-(MD1-IO12)") (class "Default")
      (node (ref "MD1") (pin "14") (pinfunction "IO12_14") (pintype "bidirectional"))
      (node (ref "R8") (pin "1") (pinfunction "1_1") (pintype "passive"))
    )
    (net (code "51") (name "Net-(MD1-IO13)") (class "Default")
      (node (ref "MD1") (pin "16") (pinfunction "IO13_16") (pintype "bidirectional"))
      (node (ref "R9") (pin "1") (pinfunction "1_1") (pintype "passive"))
    )
    (net (code "52") (name "Net-(MD1-IO14)") (class "Default")
      (node (ref "MD1") (pin "13") (pinfunction "IO14_13") (pintype "bidirectional"))
      (node (ref "R10") (pin "1") (pinfunction "1_1") (pintype "passive"))
    )
    (net (code "53") (name "Net-(MD1-IO15)") (class "Default")
      (node (ref "MD1") (pin "23") (pinfunction "IO15_23") (pintype "bidirectional"))
      (node (ref "R11") (pin "1") (pinfunction "1_1") (pintype "passive"))
    )
    (net (code "54") (name "Net-(MD1-IO16)") (class "Default")
      (node (ref "MD1") (pin "27") (pinfunction "IO16_27") (pintype "bidirectional"))
      (node (ref "R13") (pin "1") (pinfunction "1_1") (pintype "passive"))
    )
    (net (code "55") (name "Net-(MD1-IO17)") (class "Default")
      (node (ref "MD1") (pin "28") (pinfunction "IO17_28") (pintype "bidirectional"))
      (node (ref "R15") (pin "1") (pinfunction "1_1") (pintype "passive"))
    )
    (net (code "56") (name "Net-(MD1-IO18)") (class "Default")
      (node (ref "MD1") (pin "30") (pinfunction "IO18_30") (pintype "bidirectional"))
      (node (ref "R17") (pin "1") (pinfunction "1_1") (pintype "passive"))
    )
    (net (code "57") (name "Net-(MD1-IO19)") (class "Default")
      (node (ref "MD1") (pin "31") (pinfunction "IO19_31") (pintype "bidirectional"))
      (node (ref "R18") (pin "1") (pinfunction "1_1") (pintype "passive"))
    )
    (net (code "58") (name "Net-(MD1-IO22)") (class "Default")
      (node (ref "MD1") (pin "36") (pinfunction "IO22_36") (pintype "bidirectional"))
      (node (ref "R20") (pin "1") (pinfunction "1_1") (pintype "passive"))
    )
    (net (code "59") (name "Net-(MD1-IO23)") (class "Default")
      (node (ref "MD1") (pin "37") (pinfunction "IO23_37") (pintype "bidirectional"))
      (node (ref "R21") (pin "1") (pinfunction "1_1") (pintype "passive"))
    )
    (net (code "60") (name "Net-(MD1-IO25)") (class "Default")
      (node (ref "MD1") (pin "10") (pinfunction "IO25_10") (pintype "bidirectional"))
      (node (ref "R22") (pin "1") (pinfunction "1_1") (pintype "passive"))
    )
    (net (code "61") (name "Net-(MD1-IO26)") (class "Default")
      (node (ref "MD1") (pin "11") (pinfunction "IO26_11") (pintype "bidirectional"))
      (node (ref "R23") (pin "1") (pinfunction "1_1") (pintype "passive"))
    )
    (net (code "62") (name "Net-(MD1-IO27)") (class "Default")
      (node (ref "MD1") (pin "12") (pinfunction "IO27_12") (pintype "bidirectional"))
      (node (ref "R24") (pin "1") (pinfunction "1_1") (pintype "passive"))
    )
    (net (code "63") (name "Net-(MD1-IO32)") (class "Default")
      (node (ref "MD1") (pin "8") (pinfunction "IO32_8") (pintype "bidirectional"))
      (node (ref "R25") (pin "1") (pinfunction "1_1") (pintype "passive"))
    )
    (net (code "64") (name "Net-(MD1-IO33)") (class "Default")
      (node (ref "MD1") (pin "9") (pinfunction "IO33_9") (pintype "bidirectional"))
      (node (ref "R27") (pin "1") (pinfunction "1_1") (pintype "passive"))
    )
    (net (code "65") (name "Net-(MD1-IO34)") (class "Default")
      (node (ref "MD1") (pin "6") (pinfunction "IO34_6") (pintype "bidirectional"))
      (node (ref "R29") (pin "1") (pinfunction "1_1") (pintype "passive"))
    )
    (net (code "66") (name "Net-(MD1-IO35)") (class "Default")
      (node (ref "MD1") (pin "7") (pinfunction "IO35_7") (pintype "bidirectional"))
      (node (ref "R30") (pin "1") (pinfunction "1_1") (pintype "passive"))
    )
    (net (code "67") (name "Net-(MD1-RXD0)") (class "Default")
      (node (ref "MD1") (pin "34") (pinfunction "RXD0_34") (pintype "bidirectional"))
      (node (ref "R4") (pin "1") (pinfunction "1_1") (pintype "passive"))
    )
    (net (code "68") (name "Net-(MD1-TXD0)") (class "Default")
      (node (ref "MD1") (pin "35") (pinfunction "TXD0_35") (pintype "bidirectional"))
      (node (ref "R6") (pin "1") (pinfunction "1_1") (pintype "passive"))
    )
    (net (code "69") (name "Net-(Q1-B)") (class "Default")
      (node (ref "Q1") (pin "1") (pinfunction "B_1") (pintype "passive"))
      (node (ref "R31") (pin "1") (pinfunction "1_1") (pintype "passive"))
    )
    (net (code "70") (name "Net-(Q2-B)") (class "Default")
      (node (ref "Q2") (pin "1") (pinfunction "B_1") (pintype "passive"))
      (node (ref "R32") (pin "2") (pinfunction "2_2") (pintype "passive"))
      (node (ref "R34") (pin "2") (pinfunction "2_2") (pintype "passive"))
    )
    (net (code "71") (name "Net-(Q3-B)") (class "Default")
      (node (ref "Q3") (pin "1") (pinfunction "B_1") (pintype "passive"))
      (node (ref "R33") (pin "2") (pinfunction "2_2") (pintype "passive"))
    )
    (net (code "72") (name "unconnected-(LCD1-CS2-Pad5)") (class "Default")
      (node (ref "LCD1") (pin "5") (pinfunction "CS2_5") (pintype "passive+no_connect"))
    )
    (net (code "73") (name "unconnected-(LCD1-DB0-Pad14)") (class "Default")
      (node (ref "LCD1") (pin "14") (pinfunction "DB0_14") (pintype "passive+no_connect"))
    )
    (net (code "74") (name "unconnected-(LCD1-DB1-Pad13)") (class "Default")
      (node (ref "LCD1") (pin "13") (pinfunction "DB1_13") (pintype "passive+no_connect"))
    )
    (net (code "75") (name "unconnected-(LCD1-DB2-Pad12)") (class "Default")
      (node (ref "LCD1") (pin "12") (pinfunction "DB2_12") (pintype "passive+no_connect"))
    )
    (net (code "76") (name "unconnected-(LCD1-DB3-Pad11)") (class "Default")
      (node (ref "LCD1") (pin "11") (pinfunction "DB3_11") (pintype "passive+no_connect"))
    )
    (net (code "77") (name "unconnected-(LCD1-DB4-Pad10)") (class "Default")
      (node (ref "LCD1") (pin "10") (pinfunction "DB4_10") (pintype "passive+no_connect"))
    )
    (net (code "78") (name "unconnected-(LCD1-DB5-Pad9)") (class "Default")
      (node (ref "LCD1") (pin "9") (pinfunction "DB5_9") (pintype "passive+no_connect"))
    )
    (net (code "79") (name "unconnected-(LCD1-DB6-Pad8)") (class "Default")
      (node (ref "LCD1") (pin "8") (pinfunction "DB6_8") (pintype "passive+no_connect"))
    )
    (net (code "80") (name "unconnected-(LCD1-DB7-Pad7)") (class "Default")
      (node (ref "LCD1") (pin "7") (pinfunction "DB7_7") (pintype "passive+no_connect"))
    )
    (net (code "81") (name "unconnected-(LCD1-RET-Pad4)") (class "Default")
      (node (ref "LCD1") (pin "4") (pinfunction "RET_4") (pintype "passive+no_connect"))
    )
    (net (code "82") (name "unconnected-(MD1-CLK-Pad20)") (class "Default")
      (node (ref "MD1") (pin "20") (pinfunction "CLK_20") (pintype "bidirectional+no_connect"))
    )
    (net (code "83") (name "unconnected-(MD1-CMD-Pad19)") (class "Default")
      (node (ref "MD1") (pin "19") (pinfunction "CMD_19") (pintype "bidirectional+no_connect"))
    )
    (net (code "84") (name "unconnected-(MD1-NC-Pad32)") (class "Default")
      (node (ref "MD1") (pin "32") (pinfunction "NC_32") (pintype "passive+no_connect"))
    )
    (net (code "85") (name "unconnected-(MD1-SD0-Pad21)") (class "Default")
      (node (ref "MD1") (pin "21") (pinfunction "SD0_21") (pintype "bidirectional+no_connect"))
    )
    (net (code "86") (name "unconnected-(MD1-SD1-Pad22)") (class "Default")
      (node (ref "MD1") (pin "22") (pinfunction "SD1_22") (pintype "bidirectional+no_connect"))
    )
    (net (code "87") (name "unconnected-(MD1-SD2-Pad17)") (class "Default")
      (node (ref "MD1") (pin "17") (pinfunction "SD2_17") (pintype "bidirectional+no_connect"))
    )
    (net (code "88") (name "unconnected-(MD1-SD3-Pad18)") (class "Default")
      (node (ref "MD1") (pin "18") (pinfunction "SD3_18") (pintype "bidirectional+no_connect"))
    )
    (net (code "89") (name "unconnected-(MD1-SENSOR_VN-Pad5)") (class "Default")
      (node (ref "MD1") (pin "5") (pinfunction "SENSOR_VN_5") (pintype "bidirectional+no_connect"))
    )
    (net (code "90") (name "unconnected-(MD1-SENSOR_VP-Pad4)") (class "Default")
      (node (ref "MD1") (pin "4") (pinfunction "SENSOR_VP_4") (pintype "bidirectional+no_connect"))
    )
  )
)
